# UnknownSchematic.net
KiCad netlist of a schematic drawn in EAGLE
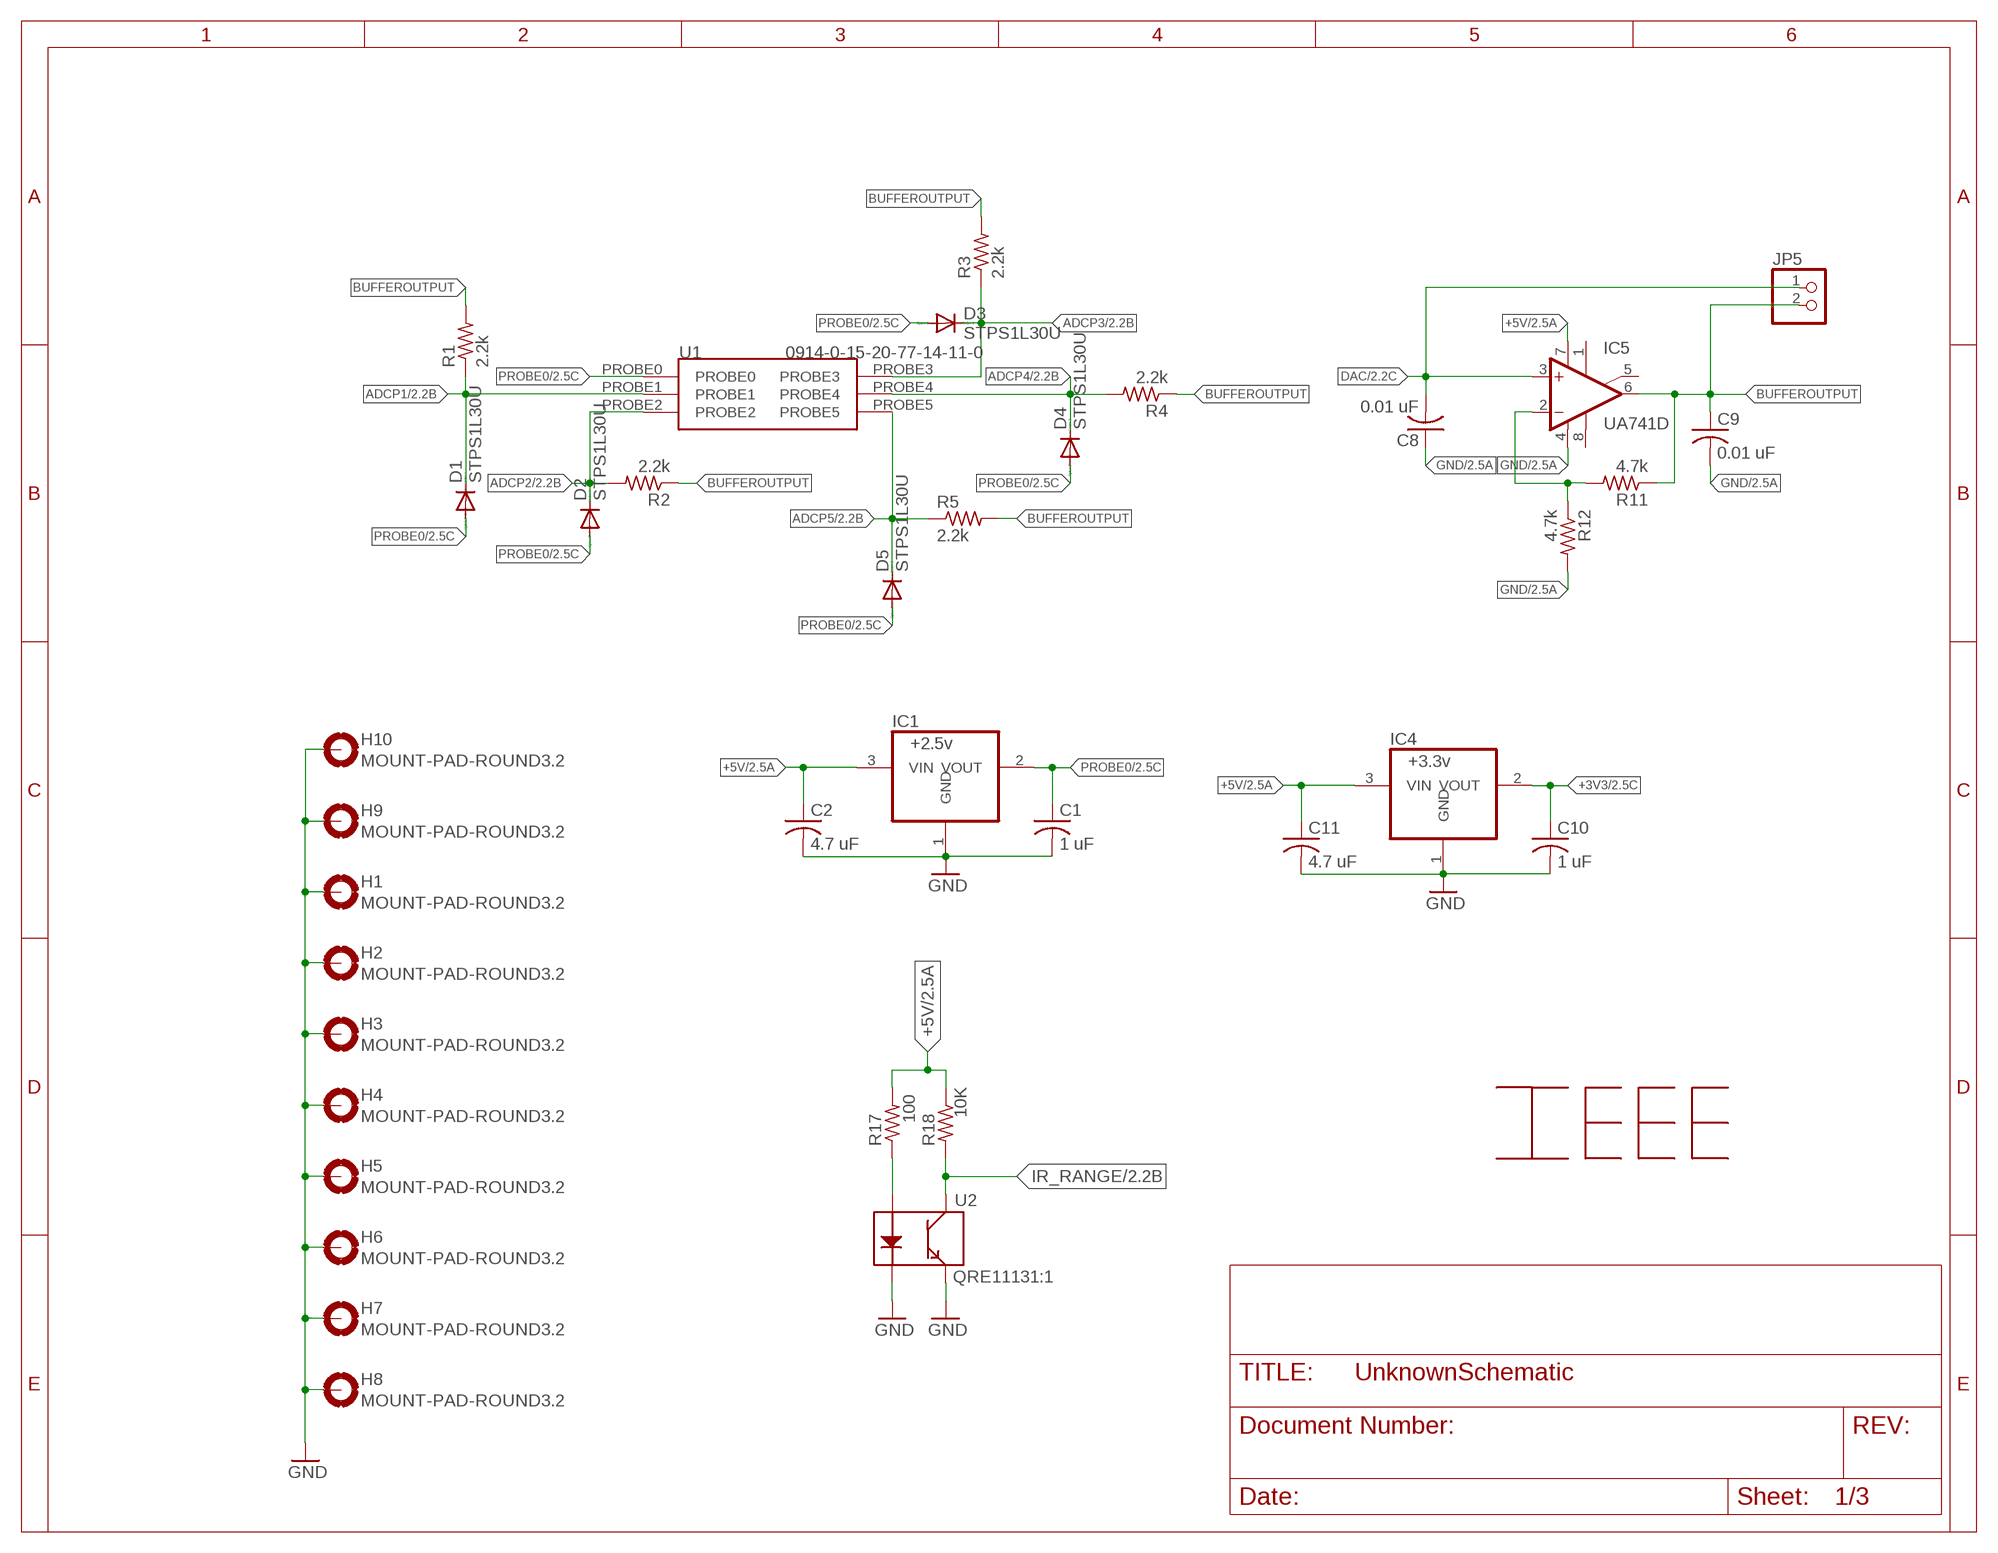
[diagram p0: schematic, sheet 1]
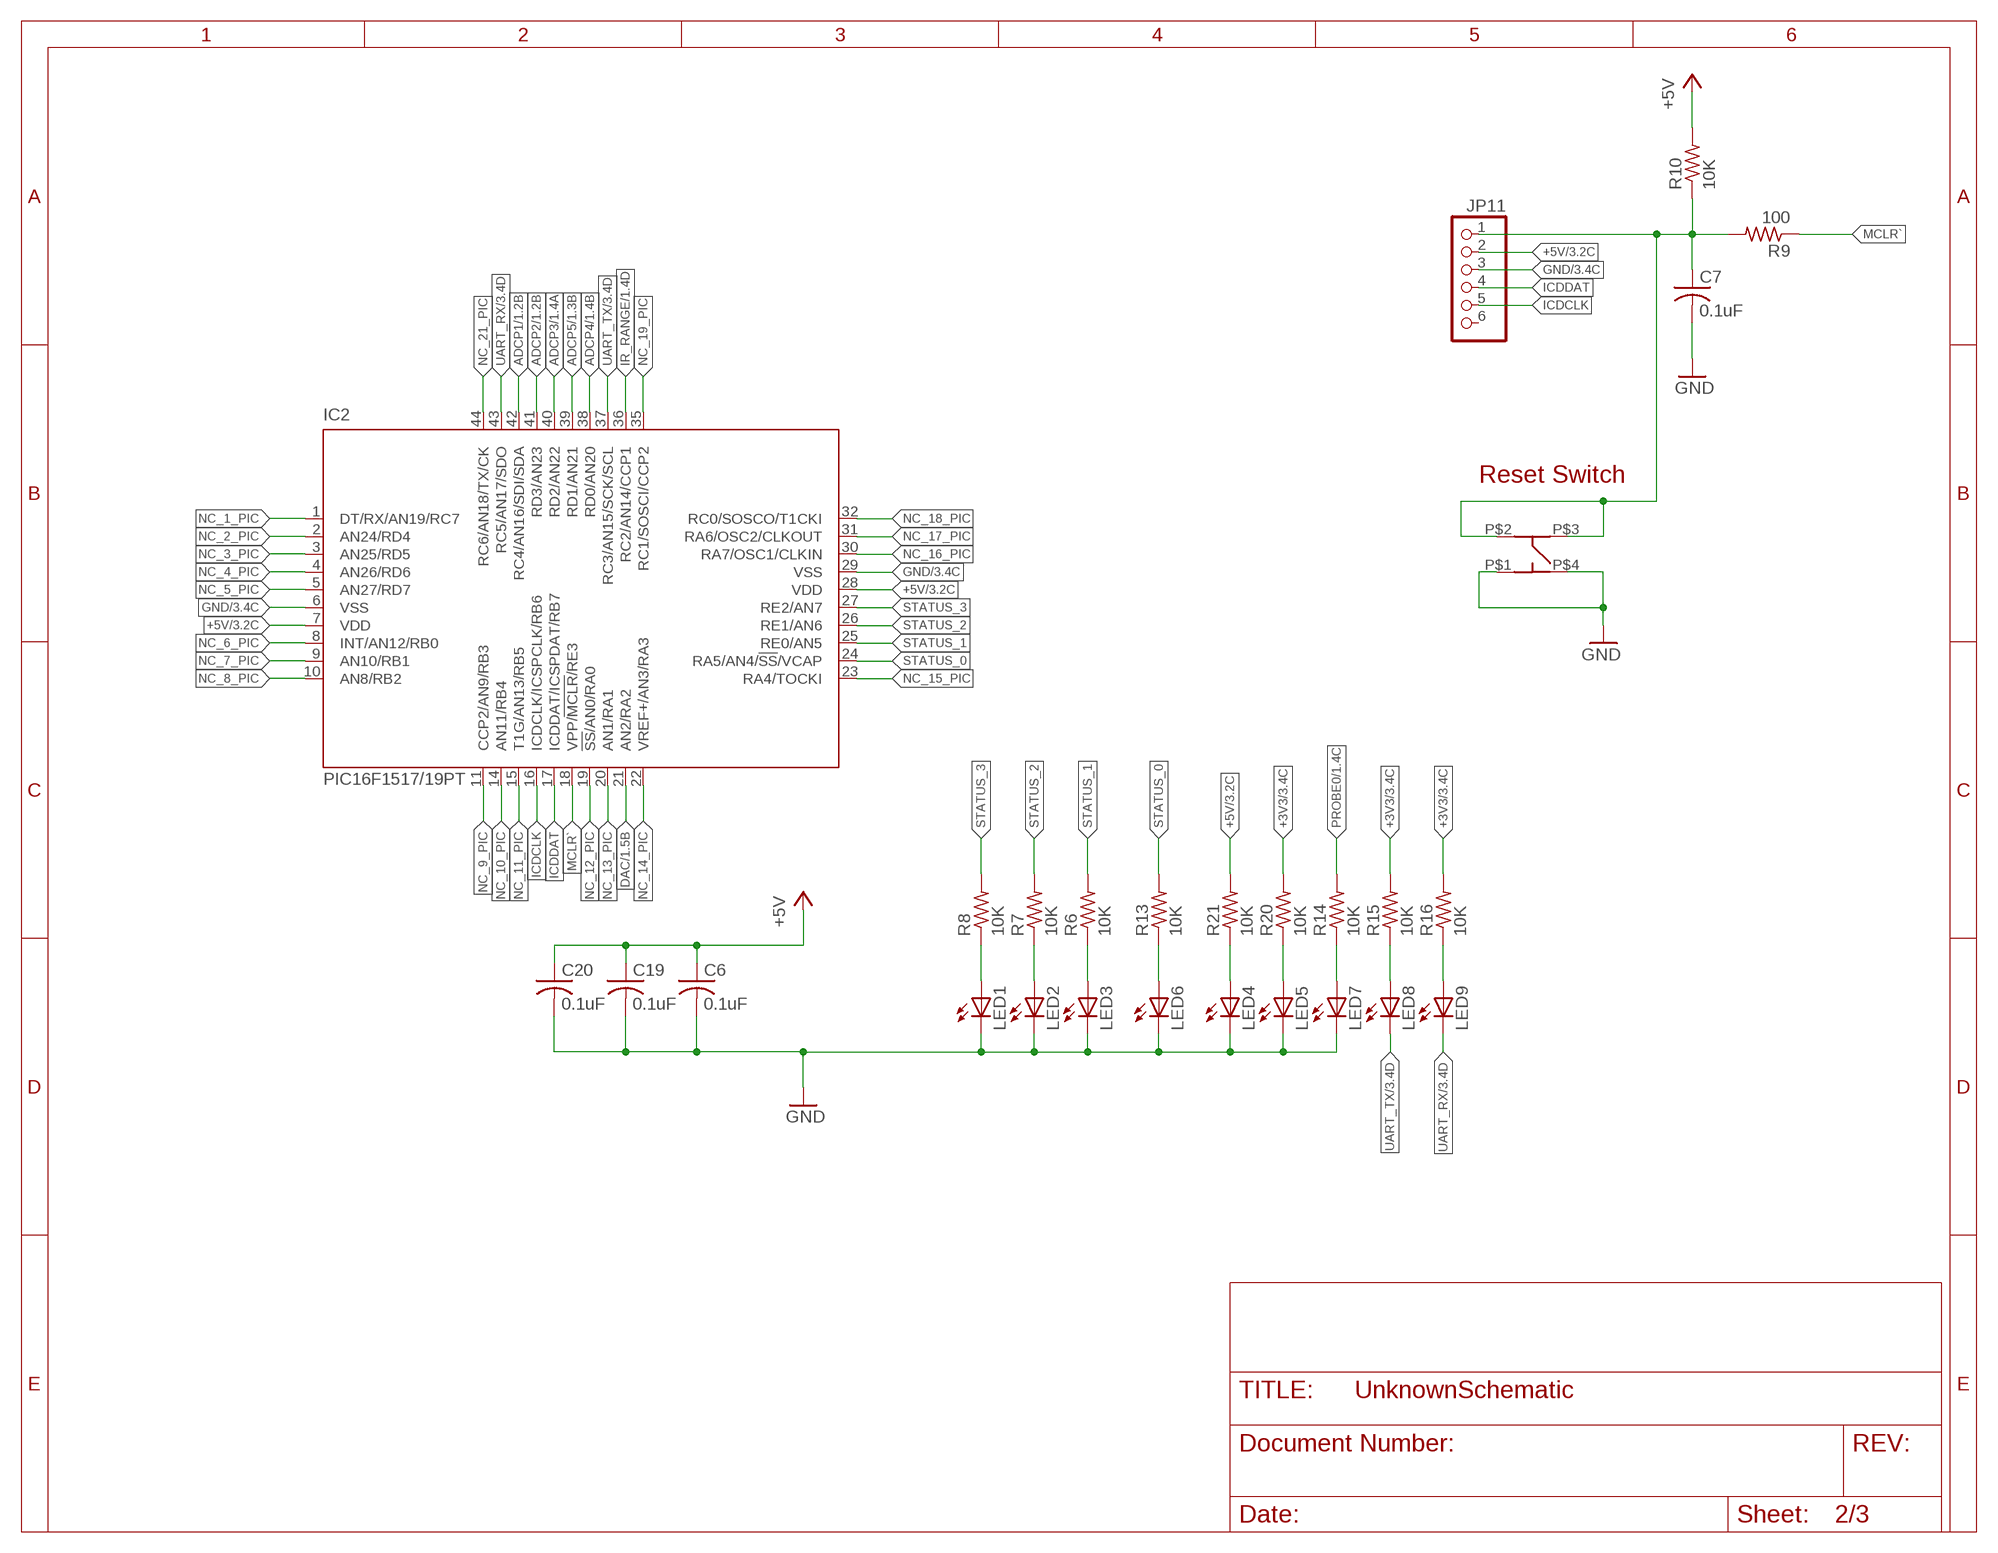
[diagram p1: schematic, sheet 2]
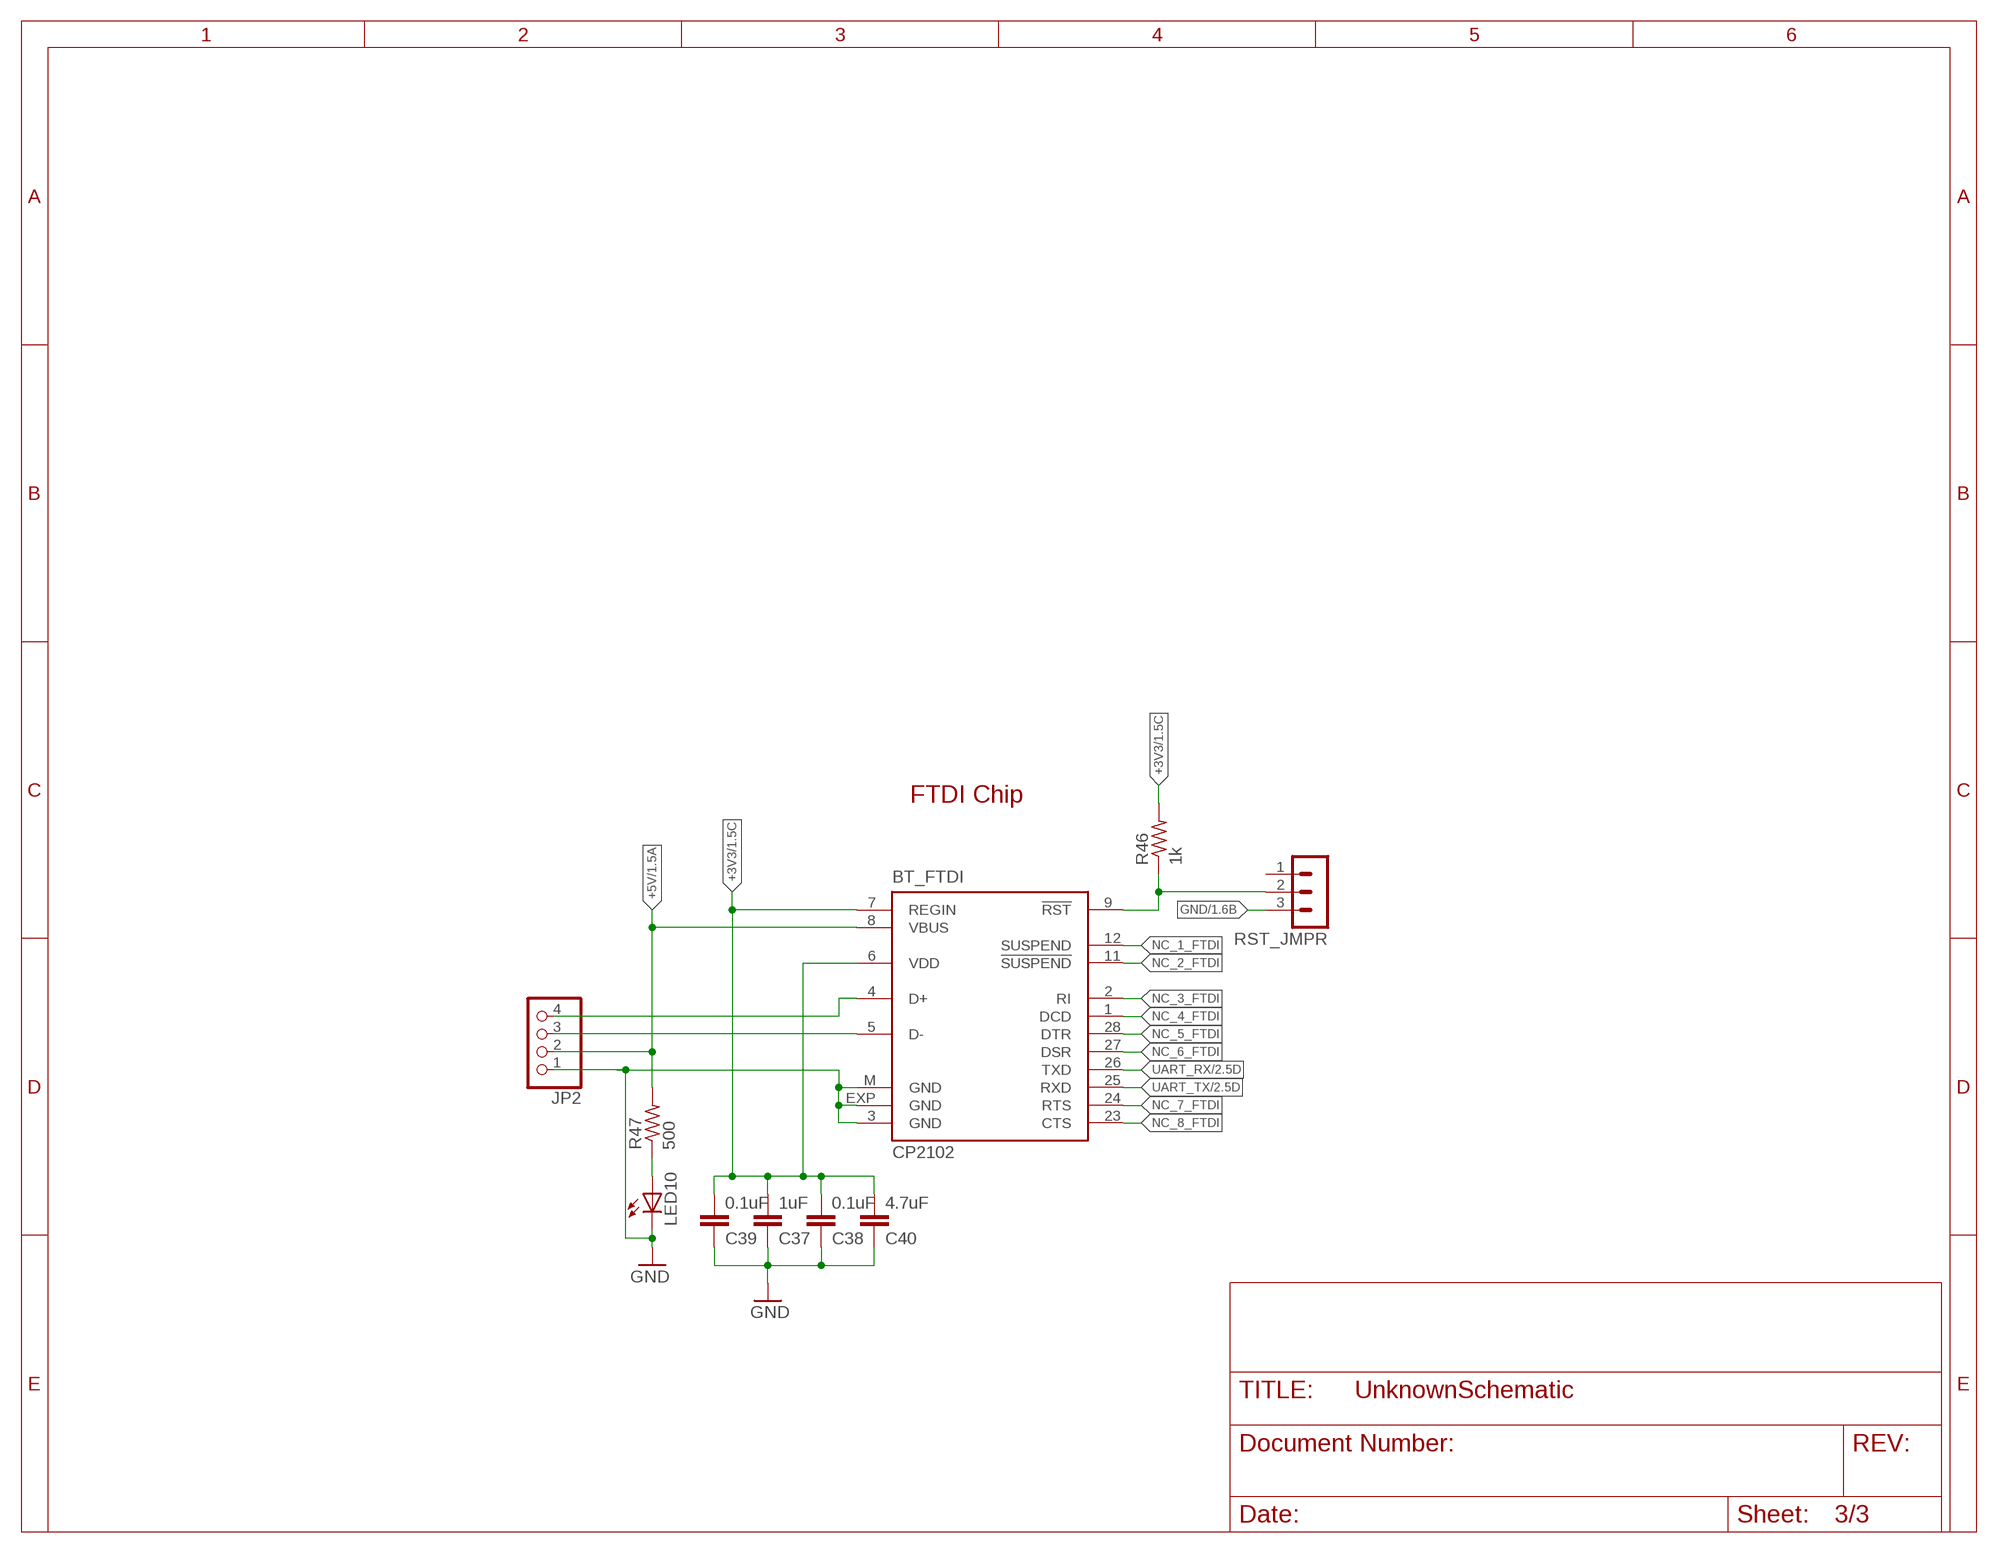
[diagram p2: schematic, sheet 3]

(export (version "E")
  (design (tool "Eeschema 10.0.6"))
  (components
    (comp (ref "BT_FTDI")
      (value "CP2102")
      (footprint "eagle-import:MLP28")
      (fields (field (name "MF") "FARNELL") (field (name "MPN") "CP2102-GM"))
      (libsource (lib "eagle-import") (part "CP2102"))
    )
    (comp (ref "C37")
      (value "1uF")
      (footprint "eagle-import:C0805")
      (libsource (lib "eagle-import") (part "C-EUC0805"))
    )
    (comp (ref "C38")
      (value "0.1uF")
      (footprint "eagle-import:C0805")
      (libsource (lib "eagle-import") (part "C-EUC0805"))
    )
    (comp (ref "C39")
      (value "0.1uF")
      (footprint "eagle-import:C0805")
      (libsource (lib "eagle-import") (part "C-EUC0805"))
    )
    (comp (ref "C40")
      (value "4.7uF")
      (footprint "eagle-import:C0805")
      (libsource (lib "eagle-import") (part "C-EUC0805"))
    )
    (comp (ref "JP2")
      (value "PINHD-1X4")
      (footprint "eagle-import:1X04")
      (libsource (lib "eagle-import") (part "PINHD-1X4"))
    )
    (comp (ref "LED10")
      (value "LEDSML0603")
      (footprint "eagle-import:SML0603")
      (libsource (lib "eagle-import") (part "LEDSML0603"))
    )
    (comp (ref "R46")
      (value "1k")
      (footprint "eagle-import:R0805")
      (libsource (lib "eagle-import") (part "resistor_R-US_R0805"))
    )
    (comp (ref "R47")
      (value "500")
      (footprint "eagle-import:R0805")
      (libsource (lib "eagle-import") (part "resistor_R-US_R0805"))
    )
    (comp (ref "RST_JMPR")
      (value "MA03-1")
      (footprint "eagle-import:MA03-1")
      (libsource (lib "eagle-import") (part "MA03-1"))
    )
    (comp (ref "C1")
      (value "1 uF")
      (footprint "eagle-import:C0805")
      (libsource (lib "eagle-import") (part "C-USC0805"))
    )
    (comp (ref "C2")
      (value "4.7 uF")
      (footprint "eagle-import:C0805")
      (libsource (lib "eagle-import") (part "C-USC0805"))
    )
    (comp (ref "C8")
      (value "0.01 uF")
      (footprint "eagle-import:C0805")
      (libsource (lib "eagle-import") (part "C-USC0805"))
    )
    (comp (ref "C9")
      (value "0.01 uF")
      (footprint "eagle-import:C0805")
      (libsource (lib "eagle-import") (part "C-USC0805"))
    )
    (comp (ref "C10")
      (value "1 uF")
      (footprint "eagle-import:C0805")
      (libsource (lib "eagle-import") (part "C-USC0805"))
    )
    (comp (ref "C11")
      (value "4.7 uF")
      (footprint "eagle-import:C0805")
      (libsource (lib "eagle-import") (part "C-USC0805"))
    )
    (comp (ref "D1")
      (value "STPS1L30U")
      (footprint "eagle-import:DO214AA")
      (libsource (lib "eagle-import") (part "DIODE-DO214AA"))
    )
    (comp (ref "D2")
      (value "STPS1L30U")
      (footprint "eagle-import:DO214AA")
      (libsource (lib "eagle-import") (part "DIODE-DO214AA"))
    )
    (comp (ref "D3")
      (value "STPS1L30U")
      (footprint "eagle-import:DO214AA")
      (libsource (lib "eagle-import") (part "DIODE-DO214AA"))
    )
    (comp (ref "D4")
      (value "STPS1L30U")
      (footprint "eagle-import:DO214AA")
      (libsource (lib "eagle-import") (part "DIODE-DO214AA"))
    )
    (comp (ref "D5")
      (value "STPS1L30U")
      (footprint "eagle-import:DO214AA")
      (libsource (lib "eagle-import") (part "DIODE-DO214AA"))
    )
    (comp (ref "H1")
      (value "MOUNT-PAD-ROUND3.2")
      (footprint "eagle-import:3,2-PAD")
      (libsource (lib "eagle-import") (part "MOUNT-PAD-ROUND3.2"))
    )
    (comp (ref "H2")
      (value "MOUNT-PAD-ROUND3.2")
      (footprint "eagle-import:3,2-PAD")
      (libsource (lib "eagle-import") (part "MOUNT-PAD-ROUND3.2"))
    )
    (comp (ref "H3")
      (value "MOUNT-PAD-ROUND3.2")
      (footprint "eagle-import:3,2-PAD")
      (libsource (lib "eagle-import") (part "MOUNT-PAD-ROUND3.2"))
    )
    (comp (ref "H4")
      (value "MOUNT-PAD-ROUND3.2")
      (footprint "eagle-import:3,2-PAD")
      (libsource (lib "eagle-import") (part "MOUNT-PAD-ROUND3.2"))
    )
    (comp (ref "H5")
      (value "MOUNT-PAD-ROUND3.2")
      (footprint "eagle-import:3,2-PAD")
      (libsource (lib "eagle-import") (part "MOUNT-PAD-ROUND3.2"))
    )
    (comp (ref "H6")
      (value "MOUNT-PAD-ROUND3.2")
      (footprint "eagle-import:3,2-PAD")
      (libsource (lib "eagle-import") (part "MOUNT-PAD-ROUND3.2"))
    )
    (comp (ref "H7")
      (value "MOUNT-PAD-ROUND3.2")
      (footprint "eagle-import:3,2-PAD")
      (libsource (lib "eagle-import") (part "MOUNT-PAD-ROUND3.2"))
    )
    (comp (ref "H8")
      (value "MOUNT-PAD-ROUND3.2")
      (footprint "eagle-import:3,2-PAD")
      (libsource (lib "eagle-import") (part "MOUNT-PAD-ROUND3.2"))
    )
    (comp (ref "H9")
      (value "MOUNT-PAD-ROUND3.2")
      (footprint "eagle-import:3,2-PAD")
      (libsource (lib "eagle-import") (part "MOUNT-PAD-ROUND3.2"))
    )
    (comp (ref "H10")
      (value "MOUNT-PAD-ROUND3.2")
      (footprint "eagle-import:3,2-PAD")
      (libsource (lib "eagle-import") (part "MOUNT-PAD-ROUND3.2"))
    )
    (comp (ref "IC1")
      (value "+2.5v")
      (footprint "eagle-import:SOT223")
      (fields (field (name "MPN") "REG1117"))
      (libsource (lib "eagle-import") (part "REG1117"))
    )
    (comp (ref "IC4")
      (value "+3.3v")
      (footprint "eagle-import:SOT223")
      (fields (field (name "MPN") "REG1117"))
      (libsource (lib "eagle-import") (part "REG1117"))
    )
    (comp (ref "IC5")
      (value "UA741D")
      (footprint "eagle-import:SO08")
      (libsource (lib "eagle-import") (part "741DUA"))
    )
    (comp (ref "JP5")
      (value "PINHD-1X2")
      (footprint "eagle-import:1X02")
      (libsource (lib "eagle-import") (part "PINHD-1X2"))
    )
    (comp (ref "R1")
      (value "2.2k")
      (footprint "eagle-import:R0805")
      (libsource (lib "eagle-import") (part "R-US_R0805"))
    )
    (comp (ref "R2")
      (value "2.2k")
      (footprint "eagle-import:R0805")
      (libsource (lib "eagle-import") (part "R-US_R0805"))
    )
    (comp (ref "R3")
      (value "2.2k")
      (footprint "eagle-import:R0805")
      (libsource (lib "eagle-import") (part "R-US_R0805"))
    )
    (comp (ref "R4")
      (value "2.2k")
      (footprint "eagle-import:R0805")
      (libsource (lib "eagle-import") (part "R-US_R0805"))
    )
    (comp (ref "R5")
      (value "2.2k")
      (footprint "eagle-import:R0805")
      (libsource (lib "eagle-import") (part "R-US_R0805"))
    )
    (comp (ref "R11")
      (value "4.7k")
      (footprint "eagle-import:R0805")
      (libsource (lib "eagle-import") (part "R-US_R0805"))
    )
    (comp (ref "R12")
      (value "4.7k")
      (footprint "eagle-import:R0805")
      (libsource (lib "eagle-import") (part "R-US_R0805"))
    )
    (comp (ref "R17")
      (value "100")
      (footprint "eagle-import:R0805")
      (libsource (lib "eagle-import") (part "R-US_R0805"))
    )
    (comp (ref "R18")
      (value "10K")
      (footprint "eagle-import:R0805")
      (libsource (lib "eagle-import") (part "R-US_R0805"))
    )
    (comp (ref "U$1")
      (value "LOGO")
      (footprint "eagle-import:IEEE-LOGO")
      (libsource (lib "eagle-import") (part "LOGO"))
    )
    (comp (ref "U1")
      (value "0914-0-15-20-77-14-11-0")
      (footprint "eagle-import:HOLE")
      (libsource (lib "eagle-import") (part "STAGE1PROBEMOUNT"))
    )
    (comp (ref "U2")
      (value "QRE11131:1")
      (footprint "eagle-import:QRE1113-1_1")
      (libsource (lib "eagle-import") (part "QRE11131{colon}1"))
    )
    (comp (ref "C6")
      (value "0.1uF")
      (footprint "eagle-import:C0805")
      (libsource (lib "eagle-import") (part "C-USC0805"))
    )
    (comp (ref "C7")
      (value "0.1uF")
      (footprint "eagle-import:C0805")
      (libsource (lib "eagle-import") (part "C-USC0805"))
    )
    (comp (ref "C19")
      (value "0.1uF")
      (footprint "eagle-import:C0805")
      (libsource (lib "eagle-import") (part "C-USC0805"))
    )
    (comp (ref "C20")
      (value "0.1uF")
      (footprint "eagle-import:C0805")
      (libsource (lib "eagle-import") (part "C-USC0805"))
    )
    (comp (ref "IC2")
      (value "PIC16F1517/19PT")
      (footprint "eagle-import:TQFP44")
      (libsource (lib "eagle-import") (part "PIC16F1517/19PT"))
    )
    (comp (ref "JP11")
      (value "PINHD-1X6/90")
      (footprint "eagle-import:1X06_90")
      (libsource (lib "eagle-import") (part "PINHD-1X6/90"))
    )
    (comp (ref "LED1")
      (value "LEDSML0603")
      (footprint "eagle-import:SML0603")
      (libsource (lib "eagle-import") (part "LEDSML0603"))
    )
    (comp (ref "LED2")
      (value "LEDSML0603")
      (footprint "eagle-import:SML0603")
      (libsource (lib "eagle-import") (part "LEDSML0603"))
    )
    (comp (ref "LED3")
      (value "LEDSML0603")
      (footprint "eagle-import:SML0603")
      (libsource (lib "eagle-import") (part "LEDSML0603"))
    )
    (comp (ref "LED4")
      (value "LEDSML0603")
      (footprint "eagle-import:SML0603")
      (libsource (lib "eagle-import") (part "LEDSML0603"))
    )
    (comp (ref "LED5")
      (value "LEDSML0603")
      (footprint "eagle-import:SML0603")
      (libsource (lib "eagle-import") (part "LEDSML0603"))
    )
    (comp (ref "LED6")
      (value "LEDSML0603")
      (footprint "eagle-import:SML0603")
      (libsource (lib "eagle-import") (part "LEDSML0603"))
    )
    (comp (ref "LED7")
      (value "LEDSML0603")
      (footprint "eagle-import:SML0603")
      (libsource (lib "eagle-import") (part "LEDSML0603"))
    )
    (comp (ref "LED8")
      (value "LEDSML0603")
      (footprint "eagle-import:SML0603")
      (libsource (lib "eagle-import") (part "LEDSML0603"))
    )
    (comp (ref "LED9")
      (value "LEDSML0603")
      (footprint "eagle-import:SML0603")
      (libsource (lib "eagle-import") (part "LEDSML0603"))
    )
    (comp (ref "R6")
      (value "10K")
      (footprint "eagle-import:R0805")
      (libsource (lib "eagle-import") (part "R-US_R0805"))
    )
    (comp (ref "R7")
      (value "10K")
      (footprint "eagle-import:R0805")
      (libsource (lib "eagle-import") (part "R-US_R0805"))
    )
    (comp (ref "R8")
      (value "10K")
      (footprint "eagle-import:R0805")
      (libsource (lib "eagle-import") (part "R-US_R0805"))
    )
    (comp (ref "R9")
      (value "100")
      (footprint "eagle-import:R1206")
      (libsource (lib "eagle-import") (part "R-US_R1206"))
    )
    (comp (ref "R10")
      (value "10K")
      (footprint "eagle-import:R1206")
      (libsource (lib "eagle-import") (part "R-US_R1206"))
    )
    (comp (ref "R13")
      (value "10K")
      (footprint "eagle-import:R0805")
      (libsource (lib "eagle-import") (part "R-US_R0805"))
    )
    (comp (ref "R14")
      (value "10K")
      (footprint "eagle-import:R0805")
      (libsource (lib "eagle-import") (part "R-US_R0805"))
    )
    (comp (ref "R15")
      (value "10K")
      (footprint "eagle-import:R0805")
      (libsource (lib "eagle-import") (part "R-US_R0805"))
    )
    (comp (ref "R16")
      (value "10K")
      (footprint "eagle-import:R0805")
      (libsource (lib "eagle-import") (part "R-US_R0805"))
    )
    (comp (ref "R20")
      (value "10K")
      (footprint "eagle-import:R0805")
      (libsource (lib "eagle-import") (part "R-US_R0805"))
    )
    (comp (ref "R21")
      (value "10K")
      (footprint "eagle-import:R0805")
      (libsource (lib "eagle-import") (part "R-US_R0805"))
    )
    (comp (ref "TOUCH_RESET")
      (value "RESET")
      (footprint "eagle-import:MC32882_FINAL")
      (libsource (lib "eagle-import") (part "MC32882_SW"))
    )
  )
  (nets
    (net (code "1") (name "+3V3") (class "Default")
      (node (ref "BT_FTDI") (pin "6") (pinfunction "VDD_6") (pintype "power_in"))
      (node (ref "BT_FTDI") (pin "7") (pinfunction "REGIN_7") (pintype "passive"))
      (node (ref "C10") (pin "1") (pinfunction "1_1") (pintype "passive"))
      (node (ref "C37") (pin "2") (pinfunction "2_2") (pintype "passive"))
      (node (ref "C38") (pin "2") (pinfunction "2_2") (pintype "passive"))
      (node (ref "C39") (pin "2") (pinfunction "2_2") (pintype "passive"))
      (node (ref "C40") (pin "2") (pinfunction "2_2") (pintype "passive"))
      (node (ref "IC4") (pin "2") (pinfunction "VOUT_2") (pintype "output"))
      (node (ref "R15") (pin "2") (pinfunction "2_2") (pintype "passive"))
      (node (ref "R16") (pin "2") (pinfunction "2_2") (pintype "passive"))
      (node (ref "R20") (pin "2") (pinfunction "2_2") (pintype "passive"))
      (node (ref "R46") (pin "2") (pinfunction "2_2") (pintype "passive"))
    )
    (net (code "2") (name "+5V") (class "Default")
      (node (ref "BT_FTDI") (pin "8") (pinfunction "VBUS_8") (pintype "input"))
      (node (ref "C11") (pin "1") (pinfunction "1_1") (pintype "passive"))
      (node (ref "C19") (pin "1") (pinfunction "1_1") (pintype "passive"))
      (node (ref "C2") (pin "1") (pinfunction "1_1") (pintype "passive"))
      (node (ref "C20") (pin "1") (pinfunction "1_1") (pintype "passive"))
      (node (ref "C6") (pin "1") (pinfunction "1_1") (pintype "passive"))
      (node (ref "IC1") (pin "3") (pinfunction "VIN_3") (pintype "input"))
      (node (ref "IC2") (pin "28") (pinfunction "VDD_28") (pintype "power_in"))
      (node (ref "IC2") (pin "7") (pinfunction "VDD_7") (pintype "power_in"))
      (node (ref "IC4") (pin "3") (pinfunction "VIN_3") (pintype "input"))
      (node (ref "IC5") (pin "7") (pinfunction "V+_7") (pintype "power_in"))
      (node (ref "JP11") (pin "2") (pinfunction "2_2") (pintype "passive"))
      (node (ref "JP2") (pin "2") (pinfunction "2_2") (pintype "passive"))
      (node (ref "R10") (pin "2") (pinfunction "2_2") (pintype "passive"))
      (node (ref "R17") (pin "2") (pinfunction "2_2") (pintype "passive"))
      (node (ref "R18") (pin "1") (pinfunction "1_1") (pintype "passive"))
      (node (ref "R21") (pin "2") (pinfunction "2_2") (pintype "passive"))
      (node (ref "R47") (pin "2") (pinfunction "2_2") (pintype "passive"))
    )
    (net (code "3") (name "ADCP1") (class "Default")
      (node (ref "D1") (pin "C") (pinfunction "C_C") (pintype "passive"))
      (node (ref "IC2") (pin "42") (pinfunction "RC4/AN16/SDI/SDA_42") (pintype "bidirectional"))
      (node (ref "R1") (pin "1") (pinfunction "1_1") (pintype "passive"))
      (node (ref "U1") (pin "PROBE1") (pinfunction "PROBE1_PROBE1") (pintype "bidirectional"))
    )
    (net (code "4") (name "ADCP2") (class "Default")
      (node (ref "D2") (pin "C") (pinfunction "C_C") (pintype "passive"))
      (node (ref "IC2") (pin "41") (pinfunction "RD3/AN23_41") (pintype "bidirectional"))
      (node (ref "R2") (pin "2") (pinfunction "2_2") (pintype "passive"))
      (node (ref "U1") (pin "PROBE2") (pinfunction "PROBE2_PROBE2") (pintype "bidirectional"))
    )
    (net (code "5") (name "ADCP3") (class "Default")
      (node (ref "D3") (pin "C") (pinfunction "C_C") (pintype "passive"))
      (node (ref "IC2") (pin "40") (pinfunction "RD2/AN22_40") (pintype "bidirectional"))
      (node (ref "R3") (pin "1") (pinfunction "1_1") (pintype "passive"))
      (node (ref "U1") (pin "PROBE3") (pinfunction "PROBE3_PROBE3") (pintype "bidirectional"))
    )
    (net (code "6") (name "ADCP4") (class "Default")
      (node (ref "D4") (pin "C") (pinfunction "C_C") (pintype "passive"))
      (node (ref "IC2") (pin "38") (pinfunction "RD0/AN20_38") (pintype "bidirectional"))
      (node (ref "R4") (pin "2") (pinfunction "2_2") (pintype "passive"))
      (node (ref "U1") (pin "PROBE4") (pinfunction "PROBE4_PROBE4") (pintype "bidirectional"))
    )
    (net (code "7") (name "ADCP5") (class "Default")
      (node (ref "D5") (pin "C") (pinfunction "C_C") (pintype "passive"))
      (node (ref "IC2") (pin "39") (pinfunction "RD1/AN21_39") (pintype "bidirectional"))
      (node (ref "R5") (pin "1") (pinfunction "1_1") (pintype "passive"))
      (node (ref "U1") (pin "PROBE5") (pinfunction "PROBE5_PROBE5") (pintype "bidirectional"))
    )
    (net (code "8") (name "BUFFEROUTPUT") (class "Default")
      (node (ref "C9") (pin "1") (pinfunction "1_1") (pintype "passive"))
      (node (ref "IC5") (pin "6") (pinfunction "OUT_6") (pintype "output"))
      (node (ref "JP5") (pin "2") (pinfunction "2_2") (pintype "passive"))
      (node (ref "R1") (pin "2") (pinfunction "2_2") (pintype "passive"))
      (node (ref "R11") (pin "1") (pinfunction "1_1") (pintype "passive"))
      (node (ref "R2") (pin "1") (pinfunction "1_1") (pintype "passive"))
      (node (ref "R3") (pin "2") (pinfunction "2_2") (pintype "passive"))
      (node (ref "R4") (pin "1") (pinfunction "1_1") (pintype "passive"))
      (node (ref "R5") (pin "2") (pinfunction "2_2") (pintype "passive"))
    )
    (net (code "9") (name "DAC") (class "Default")
      (node (ref "C8") (pin "2") (pinfunction "2_2") (pintype "passive"))
      (node (ref "IC2") (pin "21") (pinfunction "AN2/RA2_21") (pintype "bidirectional"))
      (node (ref "IC5") (pin "3") (pinfunction "+IN_3") (pintype "input"))
      (node (ref "JP5") (pin "1") (pinfunction "1_1") (pintype "passive"))
    )
    (net (code "10") (name "GND") (class "Default")
      (node (ref "BT_FTDI") (pin "3") (pinfunction "GND_3") (pintype "power_in"))
      (node (ref "BT_FTDI") (pin "EXP") (pinfunction "GND_EXP") (pintype "power_in"))
      (node (ref "BT_FTDI") (pin "M") (pinfunction "GND_M") (pintype "power_in"))
      (node (ref "C1") (pin "2") (pinfunction "2_2") (pintype "passive"))
      (node (ref "C10") (pin "2") (pinfunction "2_2") (pintype "passive"))
      (node (ref "C11") (pin "2") (pinfunction "2_2") (pintype "passive"))
      (node (ref "C19") (pin "2") (pinfunction "2_2") (pintype "passive"))
      (node (ref "C2") (pin "2") (pinfunction "2_2") (pintype "passive"))
      (node (ref "C20") (pin "2") (pinfunction "2_2") (pintype "passive"))
      (node (ref "C37") (pin "1") (pinfunction "1_1") (pintype "passive"))
      (node (ref "C38") (pin "1") (pinfunction "1_1") (pintype "passive"))
      (node (ref "C39") (pin "1") (pinfunction "1_1") (pintype "passive"))
      (node (ref "C40") (pin "1") (pinfunction "1_1") (pintype "passive"))
      (node (ref "C6") (pin "2") (pinfunction "2_2") (pintype "passive"))
      (node (ref "C7") (pin "2") (pinfunction "2_2") (pintype "passive"))
      (node (ref "C8") (pin "1") (pinfunction "1_1") (pintype "passive"))
      (node (ref "C9") (pin "2") (pinfunction "2_2") (pintype "passive"))
      (node (ref "H1") (pin "B3,2") (pinfunction "MOUNT_B3,2") (pintype "passive"))
      (node (ref "H10") (pin "B3,2") (pinfunction "MOUNT_B3,2") (pintype "passive"))
      (node (ref "H2") (pin "B3,2") (pinfunction "MOUNT_B3,2") (pintype "passive"))
      (node (ref "H3") (pin "B3,2") (pinfunction "MOUNT_B3,2") (pintype "passive"))
      (node (ref "H4") (pin "B3,2") (pinfunction "MOUNT_B3,2") (pintype "passive"))
      (node (ref "H5") (pin "B3,2") (pinfunction "MOUNT_B3,2") (pintype "passive"))
      (node (ref "H6") (pin "B3,2") (pinfunction "MOUNT_B3,2") (pintype "passive"))
      (node (ref "H7") (pin "B3,2") (pinfunction "MOUNT_B3,2") (pintype "passive"))
      (node (ref "H8") (pin "B3,2") (pinfunction "MOUNT_B3,2") (pintype "passive"))
      (node (ref "H9") (pin "B3,2") (pinfunction "MOUNT_B3,2") (pintype "passive"))
      (node (ref "IC1") (pin "1") (pinfunction "GND_1") (pintype "power_in"))
      (node (ref "IC2") (pin "29") (pinfunction "VSS_29") (pintype "power_in"))
      (node (ref "IC2") (pin "6") (pinfunction "VSS_6") (pintype "power_in"))
      (node (ref "IC4") (pin "1") (pinfunction "GND_1") (pintype "power_in"))
      (node (ref "IC5") (pin "4") (pinfunction "V-_4") (pintype "power_in"))
      (node (ref "JP11") (pin "3") (pinfunction "3_3") (pintype "passive"))
      (node (ref "JP2") (pin "1") (pinfunction "1_1") (pintype "passive"))
      (node (ref "LED1") (pin "C") (pinfunction "C_C") (pintype "passive"))
      (node (ref "LED10") (pin "C") (pinfunction "C_C") (pintype "passive"))
      (node (ref "LED2") (pin "C") (pinfunction "C_C") (pintype "passive"))
      (node (ref "LED3") (pin "C") (pinfunction "C_C") (pintype "passive"))
      (node (ref "LED4") (pin "C") (pinfunction "C_C") (pintype "passive"))
      (node (ref "LED5") (pin "C") (pinfunction "C_C") (pintype "passive"))
      (node (ref "LED6") (pin "C") (pinfunction "C_C") (pintype "passive"))
      (node (ref "LED7") (pin "C") (pinfunction "C_C") (pintype "passive"))
      (node (ref "R12") (pin "2") (pinfunction "2_2") (pintype "passive"))
      (node (ref "RST_JMPR") (pin "3") (pinfunction "3_3") (pintype "passive"))
      (node (ref "TOUCH_RESET") (pin "P$1") (pinfunction "P1_P$1") (pintype "bidirectional"))
      (node (ref "TOUCH_RESET") (pin "P$4") (pinfunction "P4_P$4") (pintype "bidirectional"))
      (node (ref "U2") (pin "2") (pinfunction "K_2") (pintype "bidirectional"))
      (node (ref "U2") (pin "4") (pinfunction "E_4") (pintype "bidirectional"))
    )
    (net (code "11") (name "ICDCLK") (class "Default")
      (node (ref "IC2") (pin "16") (pinfunction "ICDCLK/ICSPCLK/RB6_16") (pintype "bidirectional"))
      (node (ref "JP11") (pin "5") (pinfunction "5_5") (pintype "passive"))
    )
    (net (code "12") (name "ICDDAT") (class "Default")
      (node (ref "IC2") (pin "17") (pinfunction "ICDDAT/ICSPDAT/RB7_17") (pintype "bidirectional"))
      (node (ref "JP11") (pin "4") (pinfunction "4_4") (pintype "passive"))
    )
    (net (code "13") (name "IR_RANGE") (class "Default")
      (node (ref "IC2") (pin "36") (pinfunction "RC2/AN14/CCP1_36") (pintype "bidirectional"))
      (node (ref "R18") (pin "2") (pinfunction "2_2") (pintype "passive"))
      (node (ref "U2") (pin "3") (pinfunction "C_3") (pintype "bidirectional"))
    )
    (net (code "14") (name "MCLR`") (class "Default")
      (node (ref "IC2") (pin "18") (pinfunction "VPP/~{MCLR}/RE3_18") (pintype "input"))
      (node (ref "R9") (pin "1") (pinfunction "1_1") (pintype "passive"))
    )
    (net (code "15") (name "NC_1_FTDI") (class "Default")
      (node (ref "BT_FTDI") (pin "12") (pinfunction "SUSPEND_12") (pintype "output"))
    )
    (net (code "16") (name "NC_1_PIC") (class "Default")
      (node (ref "IC2") (pin "1") (pinfunction "DT/RX/AN19/RC7_1") (pintype "bidirectional"))
    )
    (net (code "17") (name "NC_2_FTDI") (class "Default")
      (node (ref "BT_FTDI") (pin "11") (pinfunction "~{SUSPEND}_11") (pintype "output"))
    )
    (net (code "18") (name "NC_2_PIC") (class "Default")
      (node (ref "IC2") (pin "2") (pinfunction "AN24/RD4_2") (pintype "bidirectional"))
    )
    (net (code "19") (name "NC_3_FTDI") (class "Default")
      (node (ref "BT_FTDI") (pin "2") (pinfunction "RI_2") (pintype "input"))
    )
    (net (code "20") (name "NC_3_PIC") (class "Default")
      (node (ref "IC2") (pin "3") (pinfunction "AN25/RD5_3") (pintype "bidirectional"))
    )
    (net (code "21") (name "NC_4_FTDI") (class "Default")
      (node (ref "BT_FTDI") (pin "1") (pinfunction "DCD_1") (pintype "input"))
    )
    (net (code "22") (name "NC_4_PIC") (class "Default")
      (node (ref "IC2") (pin "4") (pinfunction "AN26/RD6_4") (pintype "bidirectional"))
    )
    (net (code "23") (name "NC_5_FTDI") (class "Default")
      (node (ref "BT_FTDI") (pin "28") (pinfunction "DTR_28") (pintype "output"))
    )
    (net (code "24") (name "NC_5_PIC") (class "Default")
      (node (ref "IC2") (pin "5") (pinfunction "AN27/RD7_5") (pintype "bidirectional"))
    )
    (net (code "25") (name "NC_6_FTDI") (class "Default")
      (node (ref "BT_FTDI") (pin "27") (pinfunction "DSR_27") (pintype "input"))
    )
    (net (code "26") (name "NC_6_PIC") (class "Default")
      (node (ref "IC2") (pin "8") (pinfunction "INT/AN12/RB0_8") (pintype "bidirectional"))
    )
    (net (code "27") (name "NC_7_FTDI") (class "Default")
      (node (ref "BT_FTDI") (pin "24") (pinfunction "RTS_24") (pintype "output"))
    )
    (net (code "28") (name "NC_7_PIC") (class "Default")
      (node (ref "IC2") (pin "9") (pinfunction "AN10/RB1_9") (pintype "bidirectional"))
    )
    (net (code "29") (name "NC_8_FTDI") (class "Default")
      (node (ref "BT_FTDI") (pin "23") (pinfunction "CTS_23") (pintype "input"))
    )
    (net (code "30") (name "NC_8_PIC") (class "Default")
      (node (ref "IC2") (pin "10") (pinfunction "AN8/RB2_10") (pintype "bidirectional"))
    )
    (net (code "31") (name "NC_9_PIC") (class "Default")
      (node (ref "IC2") (pin "11") (pinfunction "CCP2/AN9/RB3_11") (pintype "bidirectional"))
    )
    (net (code "32") (name "NC_10_PIC") (class "Default")
      (node (ref "IC2") (pin "14") (pinfunction "AN11/RB4_14") (pintype "bidirectional"))
    )
    (net (code "33") (name "NC_11_PIC") (class "Default")
      (node (ref "IC2") (pin "15") (pinfunction "T1G/AN13/RB5_15") (pintype "bidirectional"))
    )
    (net (code "34") (name "NC_12_PIC") (class "Default")
      (node (ref "IC2") (pin "19") (pinfunction "~{SS}/AN0/RA0_19") (pintype "bidirectional"))
    )
    (net (code "35") (name "NC_13_PIC") (class "Default")
      (node (ref "IC2") (pin "20") (pinfunction "AN1/RA1_20") (pintype "bidirectional"))
    )
    (net (code "36") (name "NC_14_PIC") (class "Default")
      (node (ref "IC2") (pin "22") (pinfunction "VREF+/AN3/RA3_22") (pintype "bidirectional"))
    )
    (net (code "37") (name "NC_15_PIC") (class "Default")
      (node (ref "IC2") (pin "23") (pinfunction "RA4/TOCKI_23") (pintype "bidirectional"))
    )
    (net (code "38") (name "NC_16_PIC") (class "Default")
      (node (ref "IC2") (pin "30") (pinfunction "RA7/OSC1/CLKIN_30") (pintype "bidirectional"))
    )
    (net (code "39") (name "NC_17_PIC") (class "Default")
      (node (ref "IC2") (pin "31") (pinfunction "RA6/OSC2/CLKOUT_31") (pintype "bidirectional"))
    )
    (net (code "40") (name "NC_18_PIC") (class "Default")
      (node (ref "IC2") (pin "32") (pinfunction "RC0/SOSCO/T1CKI_32") (pintype "bidirectional"))
    )
    (net (code "41") (name "NC_19_PIC") (class "Default")
      (node (ref "IC2") (pin "35") (pinfunction "RC1/SOSCI/CCP2_35") (pintype "bidirectional"))
    )
    (net (code "42") (name "NC_21_PIC") (class "Default")
      (node (ref "IC2") (pin "44") (pinfunction "RC6/AN18/TX/CK_44") (pintype "bidirectional"))
    )
    (net (code "43") (name "Net-(BT_FTDI-D+)") (class "Default")
      (node (ref "BT_FTDI") (pin "4") (pinfunction "D+_4") (pintype "bidirectional"))
      (node (ref "JP2") (pin "4") (pinfunction "4_4") (pintype "passive"))
    )
    (net (code "44") (name "Net-(BT_FTDI-D-)") (class "Default")
      (node (ref "BT_FTDI") (pin "5") (pinfunction "D-_5") (pintype "bidirectional"))
      (node (ref "JP2") (pin "3") (pinfunction "3_3") (pintype "passive"))
    )
    (net (code "45") (name "Net-(BT_FTDI-~{RST})") (class "Default")
      (node (ref "BT_FTDI") (pin "9") (pinfunction "~{RST}_9") (pintype "bidirectional"))
      (node (ref "R46") (pin "1") (pinfunction "1_1") (pintype "passive"))
      (node (ref "RST_JMPR") (pin "2") (pinfunction "2_2") (pintype "passive"))
    )
    (net (code "46") (name "Net-(IC5--IN)") (class "Default")
      (node (ref "IC5") (pin "2") (pinfunction "-IN_2") (pintype "input"))
      (node (ref "R11") (pin "2") (pinfunction "2_2") (pintype "passive"))
      (node (ref "R12") (pin "1") (pinfunction "1_1") (pintype "passive"))
    )
    (net (code "47") (name "Net-(LED1-PadA)") (class "Default")
      (node (ref "LED1") (pin "A") (pinfunction "A_A") (pintype "passive"))
      (node (ref "R8") (pin "1") (pinfunction "1_1") (pintype "passive"))
    )
    (net (code "48") (name "Net-(LED2-PadA)") (class "Default")
      (node (ref "LED2") (pin "A") (pinfunction "A_A") (pintype "passive"))
      (node (ref "R7") (pin "1") (pinfunction "1_1") (pintype "passive"))
    )
    (net (code "49") (name "Net-(LED3-PadA)") (class "Default")
      (node (ref "LED3") (pin "A") (pinfunction "A_A") (pintype "passive"))
      (node (ref "R6") (pin "1") (pinfunction "1_1") (pintype "passive"))
    )
    (net (code "50") (name "Net-(LED4-PadA)") (class "Default")
      (node (ref "LED4") (pin "A") (pinfunction "A_A") (pintype "passive"))
      (node (ref "R21") (pin "1") (pinfunction "1_1") (pintype "passive"))
    )
    (net (code "51") (name "Net-(LED5-PadA)") (class "Default")
      (node (ref "LED5") (pin "A") (pinfunction "A_A") (pintype "passive"))
      (node (ref "R20") (pin "1") (pinfunction "1_1") (pintype "passive"))
    )
    (net (code "52") (name "Net-(LED6-PadA)") (class "Default")
      (node (ref "LED6") (pin "A") (pinfunction "A_A") (pintype "passive"))
      (node (ref "R13") (pin "1") (pinfunction "1_1") (pintype "passive"))
    )
    (net (code "53") (name "Net-(LED7-PadA)") (class "Default")
      (node (ref "LED7") (pin "A") (pinfunction "A_A") (pintype "passive"))
      (node (ref "R14") (pin "1") (pinfunction "1_1") (pintype "passive"))
    )
    (net (code "54") (name "Net-(LED8-PadA)") (class "Default")
      (node (ref "LED8") (pin "A") (pinfunction "A_A") (pintype "passive"))
      (node (ref "R15") (pin "1") (pinfunction "1_1") (pintype "passive"))
    )
    (net (code "55") (name "Net-(LED9-PadA)") (class "Default")
      (node (ref "LED9") (pin "A") (pinfunction "A_A") (pintype "passive"))
      (node (ref "R16") (pin "1") (pinfunction "1_1") (pintype "passive"))
    )
    (net (code "56") (name "Net-(LED10-PadA)") (class "Default")
      (node (ref "LED10") (pin "A") (pinfunction "A_A") (pintype "passive"))
      (node (ref "R47") (pin "1") (pinfunction "1_1") (pintype "passive"))
    )
    (net (code "57") (name "Net-(TOUCH_RESET-P2)") (class "Default")
      (node (ref "C7") (pin "1") (pinfunction "1_1") (pintype "passive"))
      (node (ref "JP11") (pin "1") (pinfunction "1_1") (pintype "passive"))
      (node (ref "R10") (pin "1") (pinfunction "1_1") (pintype "passive"))
      (node (ref "R9") (pin "2") (pinfunction "2_2") (pintype "passive"))
      (node (ref "TOUCH_RESET") (pin "P$2") (pinfunction "P2_P$2") (pintype "bidirectional"))
      (node (ref "TOUCH_RESET") (pin "P$3") (pinfunction "P3_P$3") (pintype "bidirectional"))
    )
    (net (code "58") (name "Net-(U2-A)") (class "Default")
      (node (ref "R17") (pin "1") (pinfunction "1_1") (pintype "passive"))
      (node (ref "U2") (pin "1") (pinfunction "A_1") (pintype "bidirectional"))
    )
    (net (code "59") (name "PROBE0") (class "Default")
      (node (ref "C1") (pin "1") (pinfunction "1_1") (pintype "passive"))
      (node (ref "D1") (pin "A") (pinfunction "A_A") (pintype "passive"))
      (node (ref "D2") (pin "A") (pinfunction "A_A") (pintype "passive"))
      (node (ref "D3") (pin "A") (pinfunction "A_A") (pintype "passive"))
      (node (ref "D4") (pin "A") (pinfunction "A_A") (pintype "passive"))
      (node (ref "D5") (pin "A") (pinfunction "A_A") (pintype "passive"))
      (node (ref "IC1") (pin "2") (pinfunction "VOUT_2") (pintype "output"))
      (node (ref "R14") (pin "2") (pinfunction "2_2") (pintype "passive"))
      (node (ref "U1") (pin "PROBE0") (pinfunction "PROBE0_PROBE0") (pintype "bidirectional"))
    )
    (net (code "60") (name "STATUS_0") (class "Default")
      (node (ref "IC2") (pin "24") (pinfunction "RA5/AN4/~{SS}/VCAP_24") (pintype "bidirectional"))
      (node (ref "R13") (pin "2") (pinfunction "2_2") (pintype "passive"))
    )
    (net (code "61") (name "STATUS_1") (class "Default")
      (node (ref "IC2") (pin "25") (pinfunction "RE0/AN5_25") (pintype "bidirectional"))
      (node (ref "R6") (pin "2") (pinfunction "2_2") (pintype "passive"))
    )
    (net (code "62") (name "STATUS_2") (class "Default")
      (node (ref "IC2") (pin "26") (pinfunction "RE1/AN6_26") (pintype "bidirectional"))
      (node (ref "R7") (pin "2") (pinfunction "2_2") (pintype "passive"))
    )
    (net (code "63") (name "STATUS_3") (class "Default")
      (node (ref "IC2") (pin "27") (pinfunction "RE2/AN7_27") (pintype "bidirectional"))
      (node (ref "R8") (pin "2") (pinfunction "2_2") (pintype "passive"))
    )
    (net (code "64") (name "UART_RX") (class "Default")
      (node (ref "BT_FTDI") (pin "26") (pinfunction "TXD_26") (pintype "output"))
      (node (ref "IC2") (pin "43") (pinfunction "RC5/AN17/SDO_43") (pintype "bidirectional"))
      (node (ref "LED9") (pin "C") (pinfunction "C_C") (pintype "passive"))
    )
    (net (code "65") (name "UART_TX") (class "Default")
      (node (ref "BT_FTDI") (pin "25") (pinfunction "RXD_25") (pintype "input"))
      (node (ref "IC2") (pin "37") (pinfunction "RC3/AN15/SCK/SCL_37") (pintype "bidirectional"))
      (node (ref "LED8") (pin "C") (pinfunction "C_C") (pintype "passive"))
    )
    (net (code "66") (name "unconnected-(IC5-ON1-Pad1)") (class "Default")
      (node (ref "IC5") (pin "1") (pinfunction "ON1_1") (pintype "passive"))
    )
    (net (code "67") (name "unconnected-(IC5-ON2-Pad5)") (class "Default")
      (node (ref "IC5") (pin "5") (pinfunction "ON2_5") (pintype "passive"))
    )
    (net (code "68") (name "unconnected-(IC5-OPT-Pad8)") (class "Default")
      (node (ref "IC5") (pin "8") (pinfunction "OPT_8") (pintype "passive"))
    )
    (net (code "69") (name "unconnected-(JP11-Pad6)") (class "Default")
      (node (ref "JP11") (pin "6") (pinfunction "6_6") (pintype "passive"))
    )
    (net (code "70") (name "unconnected-(RST_JMPR-Pad1)") (class "Default")
      (node (ref "RST_JMPR") (pin "1") (pinfunction "1_1") (pintype "passive"))
    )
  )
)
